# untitled.net
KiCad netlist of a schematic drawn in EAGLE
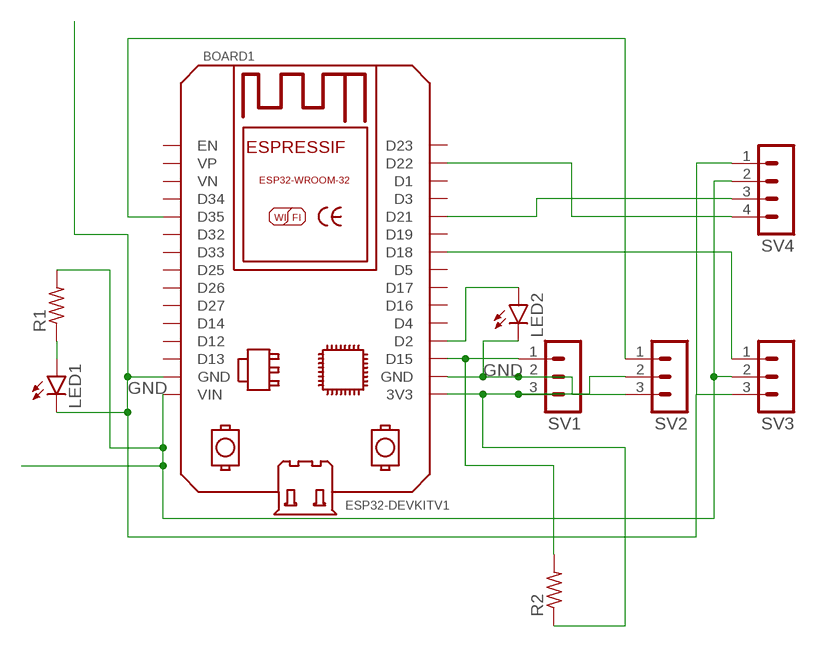
[diagram p0: schematic, sheet 1]

(export (version "E")
  (design (tool "Eeschema 10.0.6"))
  (components
    (comp (ref "BOARD1")
      (value "ESP32DEVKITV1")
      (footprint "eagle-import:ESP32-DEVKITV1")
      (libsource (lib "eagle-import") (part "ESP32DEVKITV1"))
    )
    (comp (ref "LED1")
      (value "LED5MM")
      (footprint "eagle-import:LED5MM")
      (libsource (lib "eagle-import") (part "LED5MM"))
    )
    (comp (ref "LED2")
      (value "LED5MM")
      (footprint "eagle-import:LED5MM")
      (libsource (lib "eagle-import") (part "LED5MM"))
    )
    (comp (ref "R1")
      (value "R-US_0204/7")
      (footprint "eagle-import:0204_7")
      (libsource (lib "eagle-import") (part "R-US_0204/7"))
    )
    (comp (ref "R2")
      (value "R-US_0204/7")
      (footprint "eagle-import:0204_7")
      (libsource (lib "eagle-import") (part "R-US_0204/7"))
    )
    (comp (ref "SV1")
      (value "MA03-1")
      (footprint "eagle-import:MA03-1")
      (libsource (lib "eagle-import") (part "MA03-1"))
    )
    (comp (ref "SV2")
      (value "MA03-1")
      (footprint "eagle-import:MA03-1")
      (libsource (lib "eagle-import") (part "MA03-1"))
    )
    (comp (ref "SV3")
      (value "MA03-1")
      (footprint "eagle-import:MA03-1")
      (libsource (lib "eagle-import") (part "MA03-1"))
    )
    (comp (ref "SV4")
      (value "MA04-1")
      (footprint "eagle-import:MA04-1")
      (libsource (lib "eagle-import") (part "MA04-1"))
    )
  )
  (nets
    (net (code "1") (name "/GND") (class "Default")
      (node (ref "BOARD1") (pin "GND") (pinfunction "GND_GND") (pintype "bidirectional"))
      (node (ref "BOARD1") (pin "GND@1") (pinfunction "GND_GND@1") (pintype "bidirectional"))
      (node (ref "LED1") (pin "K") (pinfunction "C_K") (pintype "passive"))
      (node (ref "LED2") (pin "K") (pinfunction "C_K") (pintype "passive"))
      (node (ref "SV1") (pin "2") (pinfunction "2_2") (pintype "passive"))
      (node (ref "SV2") (pin "3") (pinfunction "3_3") (pintype "passive"))
      (node (ref "SV3") (pin "3") (pinfunction "3_3") (pintype "passive"))
      (node (ref "SV4") (pin "1") (pinfunction "1_1") (pintype "passive"))
    )
    (net (code "2") (name "Net-(BOARD1-Pad3V3)") (class "Default")
      (node (ref "BOARD1") (pin "3V3") (pinfunction "3V3_3V3") (pintype "bidirectional"))
      (node (ref "R2") (pin "1") (pinfunction "1_1") (pintype "passive"))
      (node (ref "SV1") (pin "3") (pinfunction "3_3") (pintype "passive"))
      (node (ref "SV2") (pin "2") (pinfunction "2_2") (pintype "passive"))
    )
    (net (code "3") (name "Net-(BOARD1-PadD2)") (class "Default")
      (node (ref "BOARD1") (pin "D2") (pinfunction "D2_D2") (pintype "bidirectional"))
      (node (ref "LED2") (pin "A") (pinfunction "A_A") (pintype "passive"))
    )
    (net (code "4") (name "Net-(BOARD1-PadD15)") (class "Default")
      (node (ref "BOARD1") (pin "D15") (pinfunction "D15_D15") (pintype "bidirectional"))
      (node (ref "R2") (pin "2") (pinfunction "2_2") (pintype "passive"))
      (node (ref "SV1") (pin "1") (pinfunction "1_1") (pintype "passive"))
    )
    (net (code "5") (name "Net-(BOARD1-PadD18)") (class "Default")
      (node (ref "BOARD1") (pin "D18") (pinfunction "D18_D18") (pintype "bidirectional"))
      (node (ref "SV3") (pin "1") (pinfunction "1_1") (pintype "passive"))
    )
    (net (code "6") (name "Net-(BOARD1-PadD21)") (class "Default")
      (node (ref "BOARD1") (pin "D21") (pinfunction "D21_D21") (pintype "bidirectional"))
      (node (ref "SV4") (pin "3") (pinfunction "3_3") (pintype "passive"))
    )
    (net (code "7") (name "Net-(BOARD1-PadD22)") (class "Default")
      (node (ref "BOARD1") (pin "D22") (pinfunction "D22_D22") (pintype "bidirectional"))
      (node (ref "SV4") (pin "4") (pinfunction "4_4") (pintype "passive"))
    )
    (net (code "8") (name "Net-(BOARD1-PadD35)") (class "Default")
      (node (ref "BOARD1") (pin "D35") (pinfunction "D35_D35") (pintype "bidirectional"))
      (node (ref "SV2") (pin "1") (pinfunction "1_1") (pintype "passive"))
    )
    (net (code "9") (name "Net-(BOARD1-PadVIN)") (class "Default")
      (node (ref "BOARD1") (pin "VIN") (pinfunction "VIN_VIN") (pintype "bidirectional"))
      (node (ref "R1") (pin "2") (pinfunction "2_2") (pintype "passive"))
      (node (ref "SV3") (pin "2") (pinfunction "2_2") (pintype "passive"))
      (node (ref "SV4") (pin "2") (pinfunction "2_2") (pintype "passive"))
    )
    (net (code "10") (name "Net-(LED1-PadA)") (class "Default")
      (node (ref "LED1") (pin "A") (pinfunction "A_A") (pintype "passive"))
      (node (ref "R1") (pin "1") (pinfunction "1_1") (pintype "passive"))
    )
    (net (code "11") (name "unconnected-(BOARD1-PadD1)") (class "Default")
      (node (ref "BOARD1") (pin "D1") (pinfunction "D1_D1") (pintype "bidirectional"))
    )
    (net (code "12") (name "unconnected-(BOARD1-PadD3)") (class "Default")
      (node (ref "BOARD1") (pin "D3") (pinfunction "D3_D3") (pintype "bidirectional"))
    )
    (net (code "13") (name "unconnected-(BOARD1-PadD4)") (class "Default")
      (node (ref "BOARD1") (pin "D4") (pinfunction "D4_D4") (pintype "bidirectional"))
    )
    (net (code "14") (name "unconnected-(BOARD1-PadD5)") (class "Default")
      (node (ref "BOARD1") (pin "D5") (pinfunction "D5_D5") (pintype "bidirectional"))
    )
    (net (code "15") (name "unconnected-(BOARD1-PadD12)") (class "Default")
      (node (ref "BOARD1") (pin "D12") (pinfunction "D12_D12") (pintype "bidirectional"))
    )
    (net (code "16") (name "unconnected-(BOARD1-PadD13)") (class "Default")
      (node (ref "BOARD1") (pin "D13") (pinfunction "D13_D13") (pintype "bidirectional"))
    )
    (net (code "17") (name "unconnected-(BOARD1-PadD14)") (class "Default")
      (node (ref "BOARD1") (pin "D14") (pinfunction "D14_D14") (pintype "bidirectional"))
    )
    (net (code "18") (name "unconnected-(BOARD1-PadD16)") (class "Default")
      (node (ref "BOARD1") (pin "D16") (pinfunction "D16_D16") (pintype "bidirectional"))
    )
    (net (code "19") (name "unconnected-(BOARD1-PadD17)") (class "Default")
      (node (ref "BOARD1") (pin "D17") (pinfunction "D17_D17") (pintype "bidirectional"))
    )
    (net (code "20") (name "unconnected-(BOARD1-PadD19)") (class "Default")
      (node (ref "BOARD1") (pin "D19") (pinfunction "D19_D19") (pintype "bidirectional"))
    )
    (net (code "21") (name "unconnected-(BOARD1-PadD23)") (class "Default")
      (node (ref "BOARD1") (pin "D23") (pinfunction "D23_D23") (pintype "bidirectional"))
    )
    (net (code "22") (name "unconnected-(BOARD1-PadD25)") (class "Default")
      (node (ref "BOARD1") (pin "D25") (pinfunction "D25_D25") (pintype "bidirectional"))
    )
    (net (code "23") (name "unconnected-(BOARD1-PadD26)") (class "Default")
      (node (ref "BOARD1") (pin "D26") (pinfunction "D26_D26") (pintype "bidirectional"))
    )
    (net (code "24") (name "unconnected-(BOARD1-PadD27)") (class "Default")
      (node (ref "BOARD1") (pin "D27") (pinfunction "D27_D27") (pintype "bidirectional"))
    )
    (net (code "25") (name "unconnected-(BOARD1-PadD32)") (class "Default")
      (node (ref "BOARD1") (pin "D32") (pinfunction "D32_D32") (pintype "bidirectional"))
    )
    (net (code "26") (name "unconnected-(BOARD1-PadD33)") (class "Default")
      (node (ref "BOARD1") (pin "D33") (pinfunction "D33_D33") (pintype "bidirectional"))
    )
    (net (code "27") (name "unconnected-(BOARD1-PadD34)") (class "Default")
      (node (ref "BOARD1") (pin "D34") (pinfunction "D34_D34") (pintype "bidirectional"))
    )
    (net (code "28") (name "unconnected-(BOARD1-PadEN)") (class "Default")
      (node (ref "BOARD1") (pin "EN") (pinfunction "EN_EN") (pintype "bidirectional"))
    )
    (net (code "29") (name "unconnected-(BOARD1-PadVN)") (class "Default")
      (node (ref "BOARD1") (pin "VN") (pinfunction "VN_VN") (pintype "bidirectional"))
    )
    (net (code "30") (name "unconnected-(BOARD1-PadVP)") (class "Default")
      (node (ref "BOARD1") (pin "VP") (pinfunction "VP_VP") (pintype "bidirectional"))
    )
  )
)
